# Original_Business_Card_Schematic.net
KiCad netlist of a schematic drawn in EAGLE
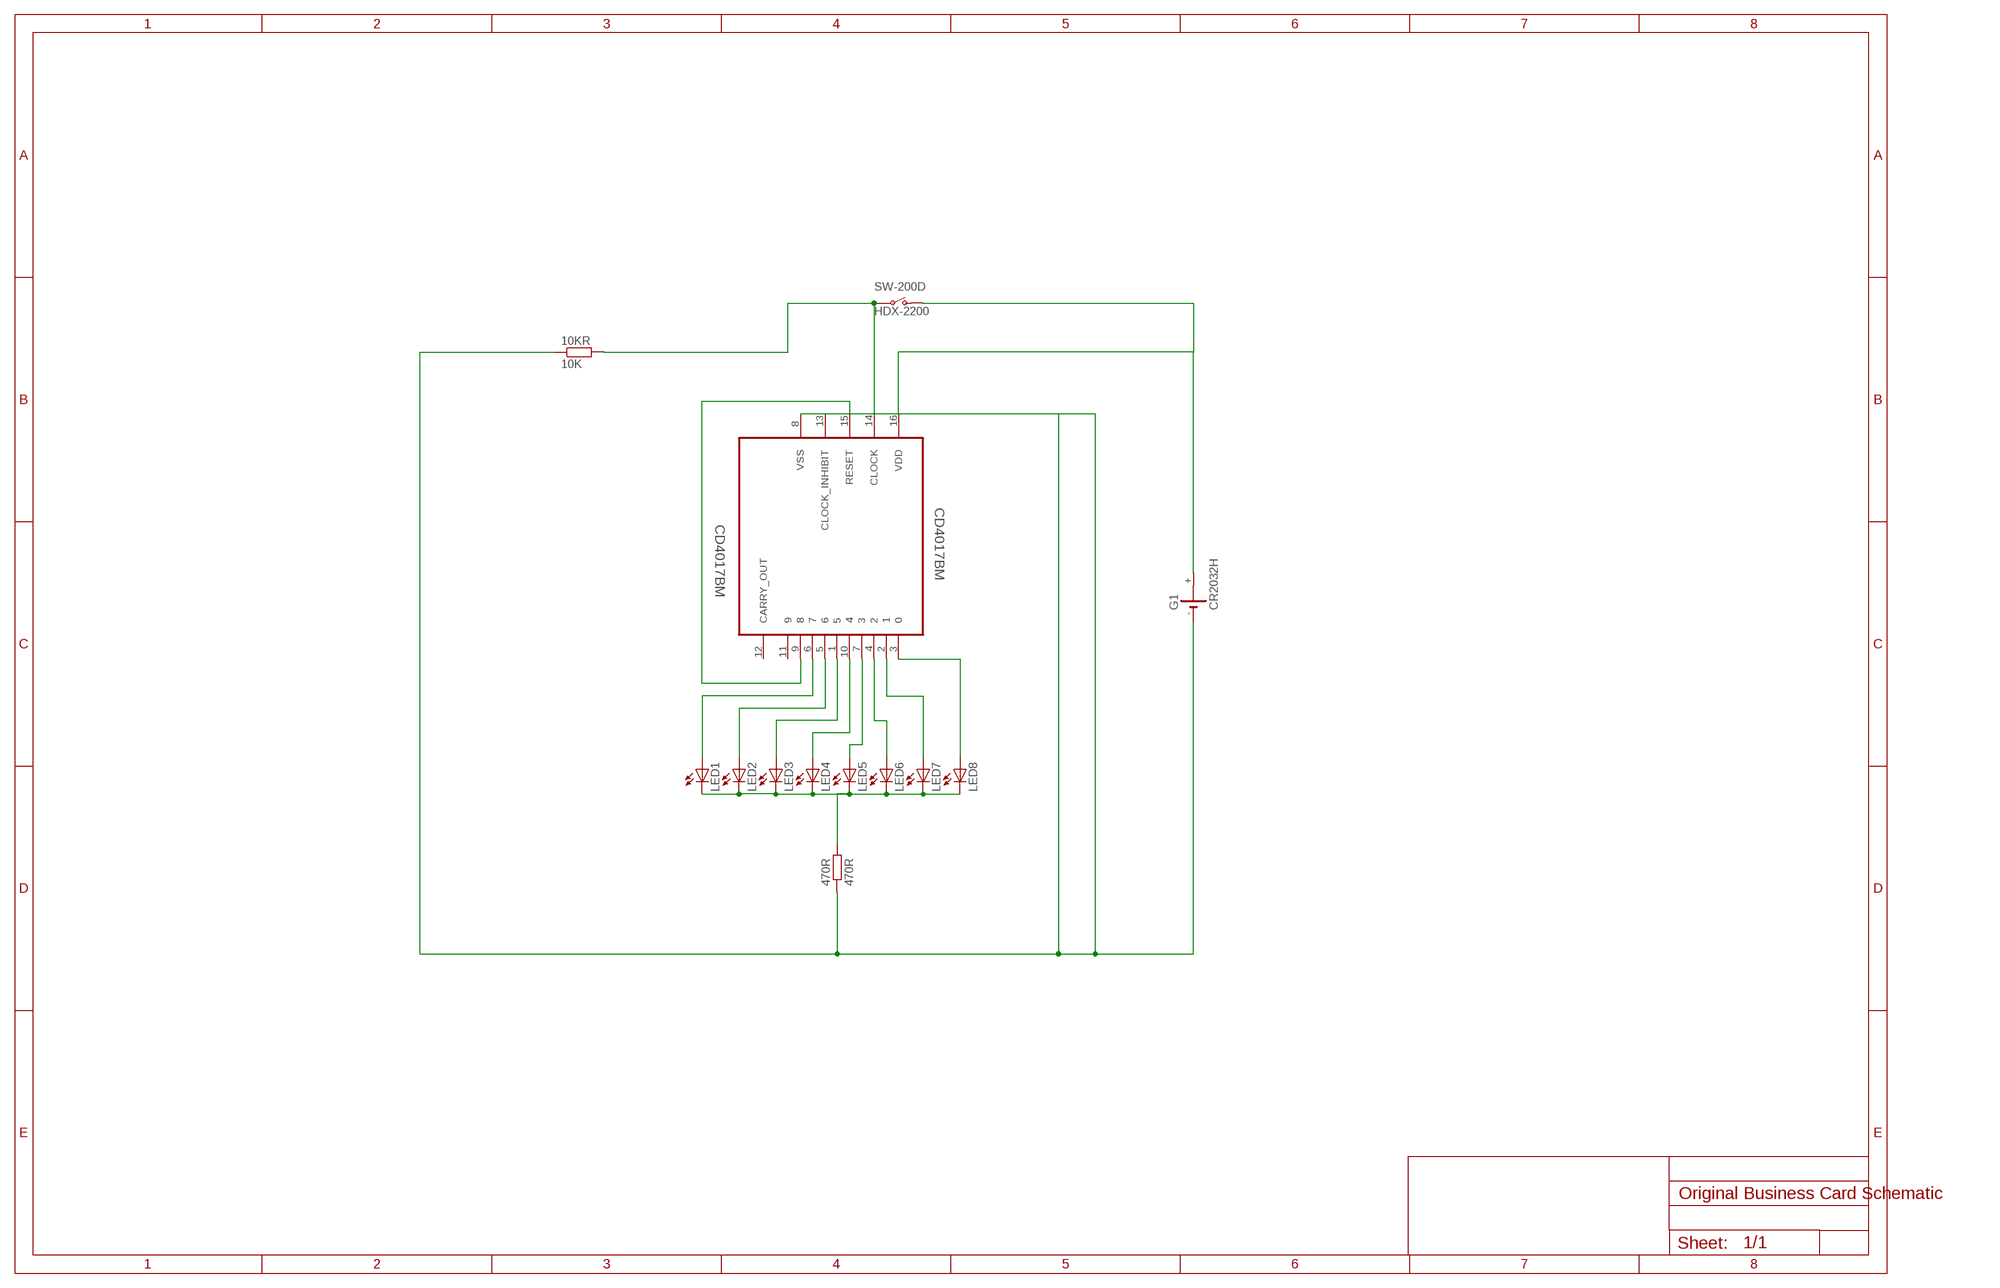
[diagram p0: schematic, sheet 1]

(export (version "E")
  (design (tool "Eeschema 10.0.6"))
  (components
    (comp (ref "10KR")
      (value "10K")
      (footprint "eagle-import:R0805")
      (libsource (lib "eagle-import") (part "R-EU_R0805"))
    )
    (comp (ref "470R")
      (value "470R")
      (footprint "eagle-import:R0603")
      (libsource (lib "eagle-import") (part "R-EU_R0603"))
    )
    (comp (ref "CD4017BM")
      (value "CD4017BM")
      (footprint "eagle-import:SOIC127P600X175-16N")
      (libsource (lib "eagle-import") (part "CD4017BM"))
    )
    (comp (ref "G1")
      (value "CR2032H")
      (footprint "eagle-import:CR2032H")
      (libsource (lib "eagle-import") (part "CR2032H"))
    )
    (comp (ref "LED1")
      (value "LEDCHIPLED_0603")
      (footprint "eagle-import:CHIPLED_0603")
      (libsource (lib "eagle-import") (part "LEDCHIPLED_0603"))
    )
    (comp (ref "LED2")
      (value "LEDCHIPLED_0603")
      (footprint "eagle-import:CHIPLED_0603")
      (libsource (lib "eagle-import") (part "LEDCHIPLED_0603"))
    )
    (comp (ref "LED3")
      (value "LEDCHIPLED_0603")
      (footprint "eagle-import:CHIPLED_0603")
      (libsource (lib "eagle-import") (part "LEDCHIPLED_0603"))
    )
    (comp (ref "LED4")
      (value "LEDCHIPLED_0603")
      (footprint "eagle-import:CHIPLED_0603")
      (libsource (lib "eagle-import") (part "LEDCHIPLED_0603"))
    )
    (comp (ref "LED5")
      (value "LEDCHIPLED_0603")
      (footprint "eagle-import:CHIPLED_0603")
      (libsource (lib "eagle-import") (part "LEDCHIPLED_0603"))
    )
    (comp (ref "LED6")
      (value "LEDCHIPLED_0603")
      (footprint "eagle-import:CHIPLED_0603")
      (libsource (lib "eagle-import") (part "LEDCHIPLED_0603"))
    )
    (comp (ref "LED7")
      (value "LEDCHIPLED_0603")
      (footprint "eagle-import:CHIPLED_0603")
      (libsource (lib "eagle-import") (part "LEDCHIPLED_0603"))
    )
    (comp (ref "LED8")
      (value "LEDCHIPLED_0603")
      (footprint "eagle-import:CHIPLED_0603")
      (libsource (lib "eagle-import") (part "LEDCHIPLED_0603"))
    )
    (comp (ref "SW-200D")
      (value "HDX-2200")
      (footprint "eagle-import:SWITCH-HORIZONTAL")
      (libsource (lib "eagle-import") (part "HDX-2200"))
    )
  )
  (nets
    (net (code "1") (name "Net-(470R-Pad2)") (class "Default")
      (node (ref "470R") (pin "2") (pinfunction "2_2") (pintype "passive"))
      (node (ref "LED1") (pin "C") (pinfunction "C_C") (pintype "passive"))
      (node (ref "LED2") (pin "C") (pinfunction "C_C") (pintype "passive"))
      (node (ref "LED3") (pin "C") (pinfunction "C_C") (pintype "passive"))
      (node (ref "LED4") (pin "C") (pinfunction "C_C") (pintype "passive"))
      (node (ref "LED5") (pin "C") (pinfunction "C_C") (pintype "passive"))
      (node (ref "LED6") (pin "C") (pinfunction "C_C") (pintype "passive"))
      (node (ref "LED7") (pin "C") (pinfunction "C_C") (pintype "passive"))
      (node (ref "LED8") (pin "C") (pinfunction "C_C") (pintype "passive"))
    )
    (net (code "2") (name "Net-(CD4017BM-0)") (class "Default")
      (node (ref "CD4017BM") (pin "3") (pinfunction "0_3") (pintype "output"))
      (node (ref "LED8") (pin "A") (pinfunction "A_A") (pintype "passive"))
    )
    (net (code "3") (name "Net-(CD4017BM-1)") (class "Default")
      (node (ref "CD4017BM") (pin "2") (pinfunction "1_2") (pintype "output"))
      (node (ref "LED7") (pin "A") (pinfunction "A_A") (pintype "passive"))
    )
    (net (code "4") (name "Net-(CD4017BM-2)") (class "Default")
      (node (ref "CD4017BM") (pin "4") (pinfunction "2_4") (pintype "output"))
      (node (ref "LED6") (pin "A") (pinfunction "A_A") (pintype "passive"))
    )
    (net (code "5") (name "Net-(CD4017BM-3)") (class "Default")
      (node (ref "CD4017BM") (pin "7") (pinfunction "3_7") (pintype "output"))
      (node (ref "LED5") (pin "A") (pinfunction "A_A") (pintype "passive"))
    )
    (net (code "6") (name "Net-(CD4017BM-4)") (class "Default")
      (node (ref "CD4017BM") (pin "10") (pinfunction "4_10") (pintype "output"))
      (node (ref "LED4") (pin "A") (pinfunction "A_A") (pintype "passive"))
    )
    (net (code "7") (name "Net-(CD4017BM-5)") (class "Default")
      (node (ref "CD4017BM") (pin "1") (pinfunction "5_1") (pintype "output"))
      (node (ref "LED3") (pin "A") (pinfunction "A_A") (pintype "passive"))
    )
    (net (code "8") (name "Net-(CD4017BM-6)") (class "Default")
      (node (ref "CD4017BM") (pin "5") (pinfunction "6_5") (pintype "output"))
      (node (ref "LED2") (pin "A") (pinfunction "A_A") (pintype "passive"))
    )
    (net (code "9") (name "Net-(CD4017BM-7)") (class "Default")
      (node (ref "CD4017BM") (pin "6") (pinfunction "7_6") (pintype "output"))
      (node (ref "LED1") (pin "A") (pinfunction "A_A") (pintype "passive"))
    )
    (net (code "10") (name "Net-(CD4017BM-8)") (class "Default")
      (node (ref "CD4017BM") (pin "15") (pinfunction "RESET_15") (pintype "input"))
      (node (ref "CD4017BM") (pin "9") (pinfunction "8_9") (pintype "output"))
    )
    (net (code "11") (name "Net-(CD4017BM-CLOCK)") (class "Default")
      (node (ref "10KR") (pin "2") (pinfunction "2_2") (pintype "passive"))
      (node (ref "CD4017BM") (pin "14") (pinfunction "CLOCK_14") (pintype "input"))
      (node (ref "SW-200D") (pin "P$2") (pinfunction "P_P$2") (pintype "passive"))
    )
    (net (code "12") (name "Net-(CD4017BM-CLOCK_INHIBIT)") (class "Default")
      (node (ref "10KR") (pin "1") (pinfunction "1_1") (pintype "passive"))
      (node (ref "470R") (pin "1") (pinfunction "1_1") (pintype "passive"))
      (node (ref "CD4017BM") (pin "13") (pinfunction "CLOCK_INHIBIT_13") (pintype "input"))
      (node (ref "CD4017BM") (pin "8") (pinfunction "VSS_8") (pintype "passive"))
      (node (ref "G1") (pin "-") (pinfunction "-_-") (pintype "passive"))
    )
    (net (code "13") (name "Net-(CD4017BM-VDD)") (class "Default")
      (node (ref "CD4017BM") (pin "16") (pinfunction "VDD_16") (pintype "input"))
      (node (ref "G1") (pin "+") (pinfunction "+_+") (pintype "passive"))
      (node (ref "SW-200D") (pin "P$1") (pinfunction "O_P$1") (pintype "passive"))
    )
    (net (code "14") (name "unconnected-(CD4017BM-9-Pad11)") (class "Default")
      (node (ref "CD4017BM") (pin "11") (pinfunction "9_11") (pintype "output"))
    )
    (net (code "15") (name "unconnected-(CD4017BM-CARRY_OUT-Pad12)") (class "Default")
      (node (ref "CD4017BM") (pin "12") (pinfunction "CARRY_OUT_12") (pintype "output"))
    )
    (net (code "16") (name "unconnected-(G1-+-Pad+@1)") (class "Default")
      (node (ref "G1") (pin "+@1") (pinfunction "+_+@1") (pintype "passive"))
    )
  )
)
